# shemLamps.net
KiCad netlist of a schematic drawn in EAGLE
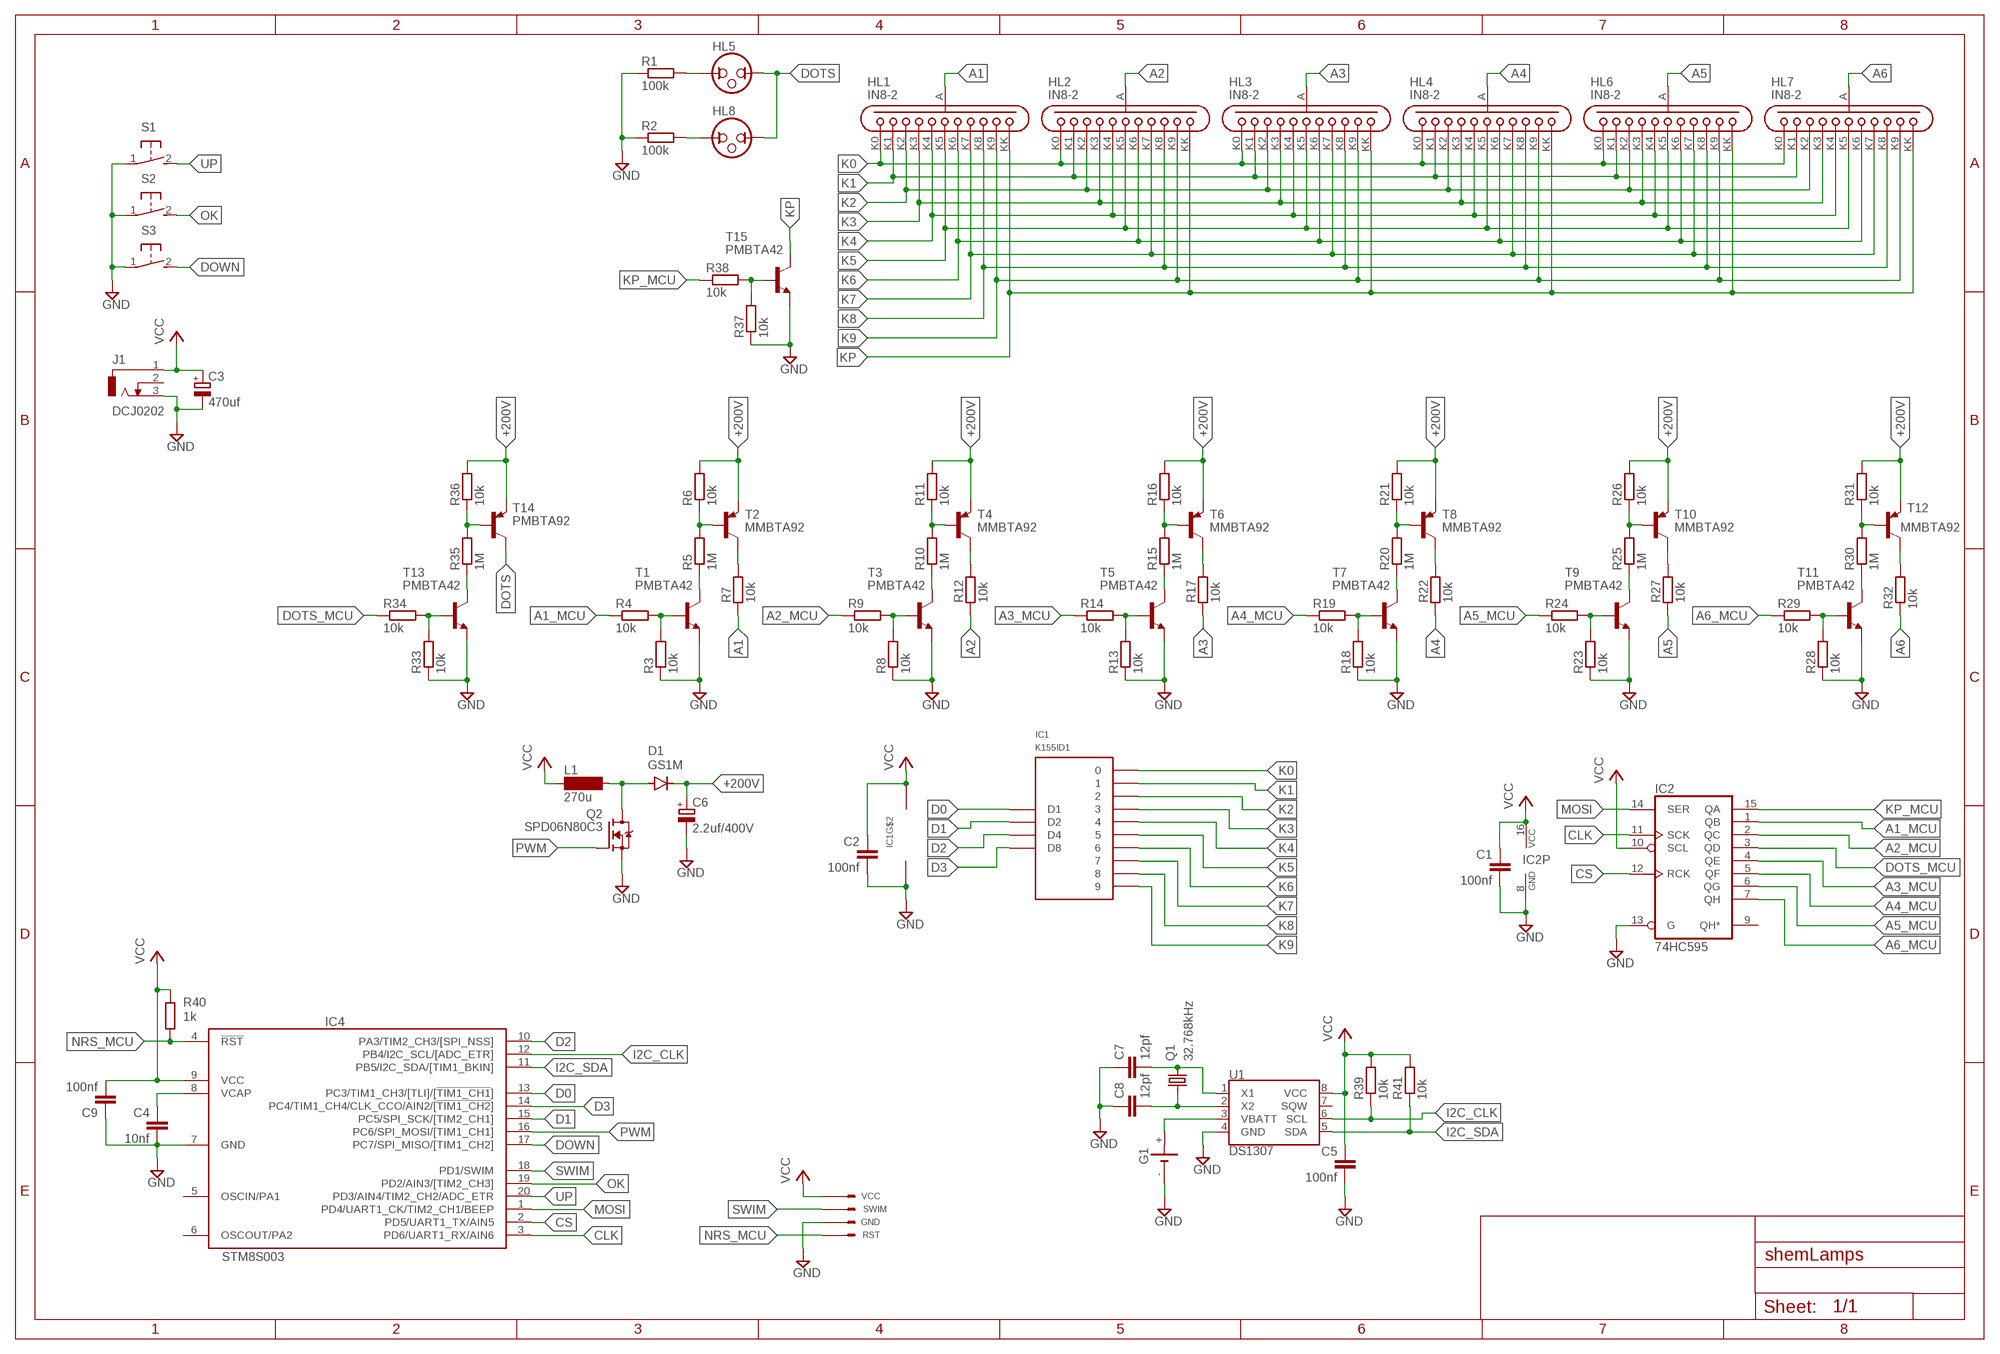
[diagram p0: schematic, sheet 1]

(export (version "E")
  (design (tool "Eeschema 10.0.6"))
  (components
    (comp (ref "C1")
      (value "100nf")
      (footprint "eagle-import:C0805")
      (libsource (lib "eagle-import") (part "CAP"))
    )
    (comp (ref "C2")
      (value "100nf")
      (footprint "eagle-import:C0805")
      (libsource (lib "eagle-import") (part "CAP"))
    )
    (comp (ref "C3")
      (value "470uf")
      (footprint "eagle-import:E3,5-8")
      (libsource (lib "eagle-import") (part "CPOL-EUE3.5-8"))
    )
    (comp (ref "C4")
      (value "10nf")
      (footprint "eagle-import:C0805")
      (libsource (lib "eagle-import") (part "CAP"))
    )
    (comp (ref "C5")
      (value "100nf")
      (footprint "eagle-import:C0805")
      (libsource (lib "eagle-import") (part "CAP"))
    )
    (comp (ref "C6")
      (value "2.2uf/400V")
      (footprint "eagle-import:E3,5-8")
      (libsource (lib "eagle-import") (part "CPOL-EUE3.5-8"))
    )
    (comp (ref "C7")
      (value "12pf")
      (footprint "eagle-import:C0805")
      (libsource (lib "eagle-import") (part "CAP"))
    )
    (comp (ref "C8")
      (value "12pf")
      (footprint "eagle-import:C0805")
      (libsource (lib "eagle-import") (part "CAP"))
    )
    (comp (ref "C9")
      (value "100nf")
      (footprint "eagle-import:C0805")
      (libsource (lib "eagle-import") (part "CAP"))
    )
    (comp (ref "D1")
      (value "GS1M")
      (footprint "eagle-import:DO-214AC")
      (libsource (lib "eagle-import") (part "DIODE-DO-214AC"))
    )
    (comp (ref "G1")
      (value "BATTERY")
      (footprint "eagle-import:CH291-1220LF_W")
      (libsource (lib "eagle-import") (part "BATTERY"))
    )
    (comp (ref "HL1")
      (value "IN8-2")
      (footprint "eagle-import:IN8-2")
      (libsource (lib "eagle-import") (part "IN8-2"))
    )
    (comp (ref "HL2")
      (value "IN8-2")
      (footprint "eagle-import:IN8-2")
      (libsource (lib "eagle-import") (part "IN8-2"))
    )
    (comp (ref "HL3")
      (value "IN8-2")
      (footprint "eagle-import:IN8-2")
      (libsource (lib "eagle-import") (part "IN8-2"))
    )
    (comp (ref "HL4")
      (value "IN8-2")
      (footprint "eagle-import:IN8-2")
      (libsource (lib "eagle-import") (part "IN8-2"))
    )
    (comp (ref "HL5")
      (value "NEON_LAMP")
      (footprint "eagle-import:NEON_LAMP")
      (libsource (lib "eagle-import") (part "NEON_LAMP"))
    )
    (comp (ref "HL6")
      (value "IN8-2")
      (footprint "eagle-import:IN8-2")
      (libsource (lib "eagle-import") (part "IN8-2"))
    )
    (comp (ref "HL7")
      (value "IN8-2")
      (footprint "eagle-import:IN8-2")
      (libsource (lib "eagle-import") (part "IN8-2"))
    )
    (comp (ref "HL8")
      (value "NEON_LAMP")
      (footprint "eagle-import:NEON_LAMP")
      (libsource (lib "eagle-import") (part "NEON_LAMP"))
    )
    (comp (ref "IC1")
      (value "K155ID1")
      (footprint "eagle-import:DIL16")
      (libsource (lib "eagle-import") (part "K155ID1"))
    )
    (comp (ref "IC2")
      (value "74HC595")
      (footprint "eagle-import:TSSOP16L")
      (libsource (lib "eagle-import") (part "74HC595"))
    )
    (comp (ref "IC4")
      (value "STM8S003")
      (footprint "eagle-import:TSSOP-20")
      (libsource (lib "eagle-import") (part "STM8S003"))
    )
    (comp (ref "J1")
      (value "DCJ0202")
      (footprint "eagle-import:DCJ0202")
      (libsource (lib "eagle-import") (part "DCJ0202"))
    )
    (comp (ref "L1")
      (value "270u")
      (footprint "eagle-import:BS11")
      (libsource (lib "eagle-import") (part "BS11"))
    )
    (comp (ref "Q1")
      (value "32.768kHz")
      (footprint "eagle-import:TC26H")
      (libsource (lib "eagle-import") (part "CRYSTALTC26H"))
    )
    (comp (ref "Q2")
      (value "SPD06N80C3")
      (footprint "eagle-import:TO252")
      (libsource (lib "eagle-import") (part "SPD06N80C3"))
    )
    (comp (ref "R1")
      (value "100k")
      (footprint "eagle-import:0207_10")
      (libsource (lib "eagle-import") (part "R-EU_0207/10"))
    )
    (comp (ref "R2")
      (value "100k")
      (footprint "eagle-import:0207_10")
      (libsource (lib "eagle-import") (part "R-EU_0207/10"))
    )
    (comp (ref "R3")
      (value "10k")
      (footprint "eagle-import:R0805")
      (libsource (lib "eagle-import") (part "RES"))
    )
    (comp (ref "R4")
      (value "10k")
      (footprint "eagle-import:R0805")
      (libsource (lib "eagle-import") (part "RES"))
    )
    (comp (ref "R5")
      (value "1M")
      (footprint "eagle-import:R0805")
      (libsource (lib "eagle-import") (part "RES"))
    )
    (comp (ref "R6")
      (value "10k")
      (footprint "eagle-import:R0805")
      (libsource (lib "eagle-import") (part "RES"))
    )
    (comp (ref "R7")
      (value "10k")
      (footprint "eagle-import:R0805")
      (libsource (lib "eagle-import") (part "RES"))
    )
    (comp (ref "R8")
      (value "10k")
      (footprint "eagle-import:R0805")
      (libsource (lib "eagle-import") (part "RES"))
    )
    (comp (ref "R9")
      (value "10k")
      (footprint "eagle-import:R0805")
      (libsource (lib "eagle-import") (part "RES"))
    )
    (comp (ref "R10")
      (value "1M")
      (footprint "eagle-import:R0805")
      (libsource (lib "eagle-import") (part "RES"))
    )
    (comp (ref "R11")
      (value "10k")
      (footprint "eagle-import:R0805")
      (libsource (lib "eagle-import") (part "RES"))
    )
    (comp (ref "R12")
      (value "10k")
      (footprint "eagle-import:R0805")
      (libsource (lib "eagle-import") (part "RES"))
    )
    (comp (ref "R13")
      (value "10k")
      (footprint "eagle-import:R0805")
      (libsource (lib "eagle-import") (part "RES"))
    )
    (comp (ref "R14")
      (value "10k")
      (footprint "eagle-import:R0805")
      (libsource (lib "eagle-import") (part "RES"))
    )
    (comp (ref "R15")
      (value "1M")
      (footprint "eagle-import:R0805")
      (libsource (lib "eagle-import") (part "RES"))
    )
    (comp (ref "R16")
      (value "10k")
      (footprint "eagle-import:R0805")
      (libsource (lib "eagle-import") (part "RES"))
    )
    (comp (ref "R17")
      (value "10k")
      (footprint "eagle-import:R0805")
      (libsource (lib "eagle-import") (part "RES"))
    )
    (comp (ref "R18")
      (value "10k")
      (footprint "eagle-import:R0805")
      (libsource (lib "eagle-import") (part "RES"))
    )
    (comp (ref "R19")
      (value "10k")
      (footprint "eagle-import:R0805")
      (libsource (lib "eagle-import") (part "RES"))
    )
    (comp (ref "R20")
      (value "1M")
      (footprint "eagle-import:R0805")
      (libsource (lib "eagle-import") (part "RES"))
    )
    (comp (ref "R21")
      (value "10k")
      (footprint "eagle-import:R0805")
      (libsource (lib "eagle-import") (part "RES"))
    )
    (comp (ref "R22")
      (value "10k")
      (footprint "eagle-import:R0805")
      (libsource (lib "eagle-import") (part "RES"))
    )
    (comp (ref "R23")
      (value "10k")
      (footprint "eagle-import:R0805")
      (libsource (lib "eagle-import") (part "RES"))
    )
    (comp (ref "R24")
      (value "10k")
      (footprint "eagle-import:R0805")
      (libsource (lib "eagle-import") (part "RES"))
    )
    (comp (ref "R25")
      (value "1M")
      (footprint "eagle-import:R0805")
      (libsource (lib "eagle-import") (part "RES"))
    )
    (comp (ref "R26")
      (value "10k")
      (footprint "eagle-import:R0805")
      (libsource (lib "eagle-import") (part "RES"))
    )
    (comp (ref "R27")
      (value "10k")
      (footprint "eagle-import:R0805")
      (libsource (lib "eagle-import") (part "RES"))
    )
    (comp (ref "R28")
      (value "10k")
      (footprint "eagle-import:R0805")
      (libsource (lib "eagle-import") (part "RES"))
    )
    (comp (ref "R29")
      (value "10k")
      (footprint "eagle-import:R0805")
      (libsource (lib "eagle-import") (part "RES"))
    )
    (comp (ref "R30")
      (value "1M")
      (footprint "eagle-import:R0805")
      (libsource (lib "eagle-import") (part "RES"))
    )
    (comp (ref "R31")
      (value "10k")
      (footprint "eagle-import:R0805")
      (libsource (lib "eagle-import") (part "RES"))
    )
    (comp (ref "R32")
      (value "10k")
      (footprint "eagle-import:R0805")
      (libsource (lib "eagle-import") (part "RES"))
    )
    (comp (ref "R33")
      (value "10k")
      (footprint "eagle-import:R0805")
      (libsource (lib "eagle-import") (part "RES"))
    )
    (comp (ref "R34")
      (value "10k")
      (footprint "eagle-import:R0805")
      (libsource (lib "eagle-import") (part "RES"))
    )
    (comp (ref "R35")
      (value "1M")
      (footprint "eagle-import:R0805")
      (libsource (lib "eagle-import") (part "RES"))
    )
    (comp (ref "R36")
      (value "10k")
      (footprint "eagle-import:R0805")
      (libsource (lib "eagle-import") (part "RES"))
    )
    (comp (ref "R37")
      (value "10k")
      (footprint "eagle-import:R0805")
      (libsource (lib "eagle-import") (part "RES"))
    )
    (comp (ref "R38")
      (value "10k")
      (footprint "eagle-import:R0805")
      (libsource (lib "eagle-import") (part "RES"))
    )
    (comp (ref "R39")
      (value "10k")
      (footprint "eagle-import:R0805")
      (libsource (lib "eagle-import") (part "RES"))
    )
    (comp (ref "R40")
      (value "1k")
      (footprint "eagle-import:R0805")
      (libsource (lib "eagle-import") (part "RES"))
    )
    (comp (ref "R41")
      (value "10k")
      (footprint "eagle-import:R0805")
      (libsource (lib "eagle-import") (part "RES"))
    )
    (comp (ref "S1")
      (value "31-XX")
      (footprint "eagle-import:B3F-31XX")
      (fields (field (name "MPN") "B3F-3100"))
      (libsource (lib "eagle-import") (part "31-XX"))
    )
    (comp (ref "S2")
      (value "31-XX")
      (footprint "eagle-import:B3F-31XX")
      (fields (field (name "MPN") "B3F-3100"))
      (libsource (lib "eagle-import") (part "31-XX"))
    )
    (comp (ref "S3")
      (value "31-XX")
      (footprint "eagle-import:B3F-31XX")
      (fields (field (name "MPN") "B3F-3100"))
      (libsource (lib "eagle-import") (part "31-XX"))
    )
    (comp (ref "SV1")
      (value "SWIM")
      (footprint "eagle-import:SWIM")
      (libsource (lib "eagle-import") (part "SWIM"))
    )
    (comp (ref "T1")
      (value "PMBTA42")
      (footprint "eagle-import:SOT23-BEC")
      (libsource (lib "eagle-import") (part "-NPN-SOT23-BECBC817-16"))
    )
    (comp (ref "T2")
      (value "MMBTA92")
      (footprint "eagle-import:SOT23-BEC")
      (libsource (lib "eagle-import") (part "-PNP-SOT23-BECBC807-16"))
    )
    (comp (ref "T3")
      (value "PMBTA42")
      (footprint "eagle-import:SOT23-BEC")
      (libsource (lib "eagle-import") (part "-NPN-SOT23-BECBC817-16"))
    )
    (comp (ref "T4")
      (value "MMBTA92")
      (footprint "eagle-import:SOT23-BEC")
      (libsource (lib "eagle-import") (part "-PNP-SOT23-BECBC807-16"))
    )
    (comp (ref "T5")
      (value "PMBTA42")
      (footprint "eagle-import:SOT23-BEC")
      (libsource (lib "eagle-import") (part "-NPN-SOT23-BECBC817-16"))
    )
    (comp (ref "T6")
      (value "MMBTA92")
      (footprint "eagle-import:SOT23-BEC")
      (libsource (lib "eagle-import") (part "-PNP-SOT23-BECBC807-16"))
    )
    (comp (ref "T7")
      (value "PMBTA42")
      (footprint "eagle-import:SOT23-BEC")
      (libsource (lib "eagle-import") (part "-NPN-SOT23-BECBC817-16"))
    )
    (comp (ref "T8")
      (value "MMBTA92")
      (footprint "eagle-import:SOT23-BEC")
      (libsource (lib "eagle-import") (part "-PNP-SOT23-BECBC807-16"))
    )
    (comp (ref "T9")
      (value "PMBTA42")
      (footprint "eagle-import:SOT23-BEC")
      (libsource (lib "eagle-import") (part "-NPN-SOT23-BECBC817-16"))
    )
    (comp (ref "T10")
      (value "MMBTA92")
      (footprint "eagle-import:SOT23-BEC")
      (libsource (lib "eagle-import") (part "-PNP-SOT23-BECBC807-16"))
    )
    (comp (ref "T11")
      (value "PMBTA42")
      (footprint "eagle-import:SOT23-BEC")
      (libsource (lib "eagle-import") (part "-NPN-SOT23-BECBC817-16"))
    )
    (comp (ref "T12")
      (value "MMBTA92")
      (footprint "eagle-import:SOT23-BEC")
      (libsource (lib "eagle-import") (part "-PNP-SOT23-BECBC807-16"))
    )
    (comp (ref "T13")
      (value "PMBTA42")
      (footprint "eagle-import:SOT23-BEC")
      (libsource (lib "eagle-import") (part "-NPN-SOT23-BECBC817-16"))
    )
    (comp (ref "T14")
      (value "PMBTA92")
      (footprint "eagle-import:SOT23-BEC")
      (libsource (lib "eagle-import") (part "-PNP-SOT23-BECBC807-16"))
    )
    (comp (ref "T15")
      (value "PMBTA42")
      (footprint "eagle-import:SOT23-BEC")
      (libsource (lib "eagle-import") (part "-NPN-SOT23-BECBC817-16"))
    )
    (comp (ref "U1")
      (value "DS1307")
      (footprint "eagle-import:SO08")
      (libsource (lib "eagle-import") (part "DS1307"))
    )
  )
  (nets
    (net (code "1") (name "+200V") (class "Default")
      (node (ref "C6") (pin "+") (pinfunction "+_+") (pintype "passive"))
      (node (ref "D1") (pin "C") (pinfunction "C_C") (pintype "passive"))
      (node (ref "R11") (pin "2") (pinfunction "2_2") (pintype "passive"))
      (node (ref "R16") (pin "2") (pinfunction "2_2") (pintype "passive"))
      (node (ref "R21") (pin "2") (pinfunction "2_2") (pintype "passive"))
      (node (ref "R26") (pin "2") (pinfunction "2_2") (pintype "passive"))
      (node (ref "R31") (pin "2") (pinfunction "2_2") (pintype "passive"))
      (node (ref "R36") (pin "2") (pinfunction "2_2") (pintype "passive"))
      (node (ref "R6") (pin "2") (pinfunction "2_2") (pintype "passive"))
      (node (ref "T10") (pin "E") (pinfunction "E_E") (pintype "passive"))
      (node (ref "T12") (pin "E") (pinfunction "E_E") (pintype "passive"))
      (node (ref "T14") (pin "E") (pinfunction "E_E") (pintype "passive"))
      (node (ref "T2") (pin "E") (pinfunction "E_E") (pintype "passive"))
      (node (ref "T4") (pin "E") (pinfunction "E_E") (pintype "passive"))
      (node (ref "T6") (pin "E") (pinfunction "E_E") (pintype "passive"))
      (node (ref "T8") (pin "E") (pinfunction "E_E") (pintype "passive"))
    )
    (net (code "2") (name "A1") (class "Default")
      (node (ref "HL1") (pin "A") (pinfunction "A_A") (pintype "passive"))
      (node (ref "R7") (pin "1") (pinfunction "1_1") (pintype "passive"))
    )
    (net (code "3") (name "A1_MCU") (class "Default")
      (node (ref "IC2") (pin "1") (pinfunction "QB_1") (pintype "tri_state"))
      (node (ref "R4") (pin "1") (pinfunction "1_1") (pintype "passive"))
    )
    (net (code "4") (name "A2") (class "Default")
      (node (ref "HL2") (pin "A") (pinfunction "A_A") (pintype "passive"))
      (node (ref "R12") (pin "1") (pinfunction "1_1") (pintype "passive"))
    )
    (net (code "5") (name "A2_MCU") (class "Default")
      (node (ref "IC2") (pin "2") (pinfunction "QC_2") (pintype "tri_state"))
      (node (ref "R9") (pin "1") (pinfunction "1_1") (pintype "passive"))
    )
    (net (code "6") (name "A3") (class "Default")
      (node (ref "HL3") (pin "A") (pinfunction "A_A") (pintype "passive"))
      (node (ref "R17") (pin "1") (pinfunction "1_1") (pintype "passive"))
    )
    (net (code "7") (name "A3_MCU") (class "Default")
      (node (ref "IC2") (pin "4") (pinfunction "QE_4") (pintype "tri_state"))
      (node (ref "R14") (pin "1") (pinfunction "1_1") (pintype "passive"))
    )
    (net (code "8") (name "A4") (class "Default")
      (node (ref "HL4") (pin "A") (pinfunction "A_A") (pintype "passive"))
      (node (ref "R22") (pin "1") (pinfunction "1_1") (pintype "passive"))
    )
    (net (code "9") (name "A4_MCU") (class "Default")
      (node (ref "IC2") (pin "5") (pinfunction "QF_5") (pintype "tri_state"))
      (node (ref "R19") (pin "1") (pinfunction "1_1") (pintype "passive"))
    )
    (net (code "10") (name "A5") (class "Default")
      (node (ref "HL6") (pin "A") (pinfunction "A_A") (pintype "passive"))
      (node (ref "R27") (pin "1") (pinfunction "1_1") (pintype "passive"))
    )
    (net (code "11") (name "A5_MCU") (class "Default")
      (node (ref "IC2") (pin "6") (pinfunction "QG_6") (pintype "tri_state"))
      (node (ref "R24") (pin "1") (pinfunction "1_1") (pintype "passive"))
    )
    (net (code "12") (name "A6") (class "Default")
      (node (ref "HL7") (pin "A") (pinfunction "A_A") (pintype "passive"))
      (node (ref "R32") (pin "1") (pinfunction "1_1") (pintype "passive"))
    )
    (net (code "13") (name "A6_MCU") (class "Default")
      (node (ref "IC2") (pin "7") (pinfunction "QH_7") (pintype "tri_state"))
      (node (ref "R29") (pin "1") (pinfunction "1_1") (pintype "passive"))
    )
    (net (code "14") (name "CLK") (class "Default")
      (node (ref "IC2") (pin "11") (pinfunction "SCK_11") (pintype "input"))
      (node (ref "IC4") (pin "3") (pinfunction "PD6/UART1_RX/AIN6_3") (pintype "bidirectional"))
    )
    (net (code "15") (name "CS") (class "Default")
      (node (ref "IC2") (pin "12") (pinfunction "RCK_12") (pintype "input"))
      (node (ref "IC4") (pin "2") (pinfunction "PD5/UART1_TX/AIN5_2") (pintype "bidirectional"))
    )
    (net (code "16") (name "D0") (class "Default")
      (node (ref "IC1") (pin "3") (pinfunction "D1_3") (pintype "input"))
      (node (ref "IC4") (pin "13") (pinfunction "PC3/TIM1_CH3/[TLI]/[~{TIM1_CH1}]_13") (pintype "bidirectional"))
    )
    (net (code "17") (name "D1") (class "Default")
      (node (ref "IC1") (pin "6") (pinfunction "D2_6") (pintype "input"))
      (node (ref "IC4") (pin "15") (pinfunction "PC5/SPI_SCK/[TIM2_CH1]_15") (pintype "bidirectional"))
    )
    (net (code "18") (name "D2") (class "Default")
      (node (ref "IC1") (pin "7") (pinfunction "D4_7") (pintype "input"))
      (node (ref "IC4") (pin "10") (pinfunction "PA3/TIM2_CH3/[SPI_NSS]_10") (pintype "bidirectional"))
    )
    (net (code "19") (name "D3") (class "Default")
      (node (ref "IC1") (pin "4") (pinfunction "D8_4") (pintype "input"))
      (node (ref "IC4") (pin "14") (pinfunction "PC4/TIM1_CH4/CLK_CCO/AIN2/[~{TIM1_CH2}]_14") (pintype "bidirectional"))
    )
    (net (code "20") (name "DOTS") (class "Default")
      (node (ref "HL5") (pin "2") (pinfunction "2_2") (pintype "passive"))
      (node (ref "HL8") (pin "2") (pinfunction "2_2") (pintype "passive"))
      (node (ref "T14") (pin "C") (pinfunction "C_C") (pintype "passive"))
    )
    (net (code "21") (name "DOTS_MCU") (class "Default")
      (node (ref "IC2") (pin "3") (pinfunction "QD_3") (pintype "tri_state"))
      (node (ref "R34") (pin "1") (pinfunction "1_1") (pintype "passive"))
    )
    (net (code "22") (name "DOWN") (class "Default")
      (node (ref "IC4") (pin "17") (pinfunction "PC7/SPI_MISO/[TIM1_CH2]_17") (pintype "bidirectional"))
      (node (ref "S3") (pin "2") (pinfunction "S_2") (pintype "passive"))
    )
    (net (code "23") (name "GND") (class "Default")
      (node (ref "C1") (pin "2") (pinfunction "2_2") (pintype "passive"))
      (node (ref "C2") (pin "2") (pinfunction "2_2") (pintype "passive"))
      (node (ref "C3") (pin "-") (pinfunction "-_-") (pintype "passive"))
      (node (ref "C4") (pin "2") (pinfunction "2_2") (pintype "passive"))
      (node (ref "C5") (pin "2") (pinfunction "2_2") (pintype "passive"))
      (node (ref "C6") (pin "-") (pinfunction "-_-") (pintype "passive"))
      (node (ref "C7") (pin "1") (pinfunction "1_1") (pintype "passive"))
      (node (ref "C8") (pin "1") (pinfunction "1_1") (pintype "passive"))
      (node (ref "C9") (pin "1") (pinfunction "1_1") (pintype "passive"))
      (node (ref "G1") (pin "-") (pinfunction "-_-") (pintype "passive"))
      (node (ref "IC1") (pin "12") (pinfunction "GND_12") (pintype "power_in"))
      (node (ref "IC2") (pin "13") (pinfunction "G_13") (pintype "input"))
      (node (ref "IC2") (pin "8") (pinfunction "GND_8") (pintype "power_in"))
      (node (ref "IC4") (pin "7") (pinfunction "GND_7") (pintype "power_in"))
      (node (ref "J1") (pin "3") (pinfunction "3_3") (pintype "passive"))
      (node (ref "Q2") (pin "2") (pinfunction "S_2") (pintype "passive"))
      (node (ref "R1") (pin "1") (pinfunction "1_1") (pintype "passive"))
      (node (ref "R13") (pin "1") (pinfunction "1_1") (pintype "passive"))
      (node (ref "R18") (pin "1") (pinfunction "1_1") (pintype "passive"))
      (node (ref "R2") (pin "1") (pinfunction "1_1") (pintype "passive"))
      (node (ref "R23") (pin "1") (pinfunction "1_1") (pintype "passive"))
      (node (ref "R28") (pin "1") (pinfunction "1_1") (pintype "passive"))
      (node (ref "R3") (pin "1") (pinfunction "1_1") (pintype "passive"))
      (node (ref "R33") (pin "1") (pinfunction "1_1") (pintype "passive"))
      (node (ref "R37") (pin "1") (pinfunction "1_1") (pintype "passive"))
      (node (ref "R8") (pin "1") (pinfunction "1_1") (pintype "passive"))
      (node (ref "S1") (pin "1") (pinfunction "P_1") (pintype "passive"))
      (node (ref "S2") (pin "1") (pinfunction "P_1") (pintype "passive"))
      (node (ref "S3") (pin "1") (pinfunction "P_1") (pintype "passive"))
      (node (ref "SV1") (pin "GND") (pinfunction "GND_GND") (pintype "power_in"))
      (node (ref "T1") (pin "E") (pinfunction "E_E") (pintype "passive"))
      (node (ref "T11") (pin "E") (pinfunction "E_E") (pintype "passive"))
      (node (ref "T13") (pin "E") (pinfunction "E_E") (pintype "passive"))
      (node (ref "T15") (pin "E") (pinfunction "E_E") (pintype "passive"))
      (node (ref "T3") (pin "E") (pinfunction "E_E") (pintype "passive"))
      (node (ref "T5") (pin "E") (pinfunction "E_E") (pintype "passive"))
      (node (ref "T7") (pin "E") (pinfunction "E_E") (pintype "passive"))
      (node (ref "T9") (pin "E") (pinfunction "E_E") (pintype "passive"))
      (node (ref "U1") (pin "4") (pinfunction "GND_4") (pintype "bidirectional"))
    )
    (net (code "24") (name "I2C_CLK") (class "Default")
      (node (ref "IC4") (pin "12") (pinfunction "PB4/I2C_SCL/[ADC_ETR]_12") (pintype "bidirectional"))
      (node (ref "R39") (pin "1") (pinfunction "1_1") (pintype "passive"))
      (node (ref "U1") (pin "6") (pinfunction "SCL_6") (pintype "bidirectional"))
    )
    (net (code "25") (name "I2C_SDA") (class "Default")
      (node (ref "IC4") (pin "11") (pinfunction "PB5/I2C_SDA/[TIM1_BKIN]_11") (pintype "bidirectional"))
      (node (ref "R41") (pin "1") (pinfunction "1_1") (pintype "passive"))
      (node (ref "U1") (pin "5") (pinfunction "SDA_5") (pintype "bidirectional"))
    )
    (net (code "26") (name "K0") (class "Default")
      (node (ref "HL1") (pin "K0") (pinfunction "K0_K0") (pintype "passive"))
      (node (ref "HL2") (pin "K0") (pinfunction "K0_K0") (pintype "passive"))
      (node (ref "HL3") (pin "K0") (pinfunction "K0_K0") (pintype "passive"))
      (node (ref "HL4") (pin "K0") (pinfunction "K0_K0") (pintype "passive"))
      (node (ref "HL6") (pin "K0") (pinfunction "K0_K0") (pintype "passive"))
      (node (ref "HL7") (pin "K0") (pinfunction "K0_K0") (pintype "passive"))
      (node (ref "IC1") (pin "16") (pinfunction "0_16") (pintype "output"))
    )
    (net (code "27") (name "K1") (class "Default")
      (node (ref "HL1") (pin "K1") (pinfunction "K1_K1") (pintype "passive"))
      (node (ref "HL2") (pin "K1") (pinfunction "K1_K1") (pintype "passive"))
      (node (ref "HL3") (pin "K1") (pinfunction "K1_K1") (pintype "passive"))
      (node (ref "HL4") (pin "K1") (pinfunction "K1_K1") (pintype "passive"))
      (node (ref "HL6") (pin "K1") (pinfunction "K1_K1") (pintype "passive"))
      (node (ref "HL7") (pin "K1") (pinfunction "K1_K1") (pintype "passive"))
      (node (ref "IC1") (pin "15") (pinfunction "1_15") (pintype "output"))
    )
    (net (code "28") (name "K2") (class "Default")
      (node (ref "HL1") (pin "K2") (pinfunction "K2_K2") (pintype "passive"))
      (node (ref "HL2") (pin "K2") (pinfunction "K2_K2") (pintype "passive"))
      (node (ref "HL3") (pin "K2") (pinfunction "K2_K2") (pintype "passive"))
      (node (ref "HL4") (pin "K2") (pinfunction "K2_K2") (pintype "passive"))
      (node (ref "HL6") (pin "K2") (pinfunction "K2_K2") (pintype "passive"))
      (node (ref "HL7") (pin "K2") (pinfunction "K2_K2") (pintype "passive"))
      (node (ref "IC1") (pin "8") (pinfunction "2_8") (pintype "output"))
    )
    (net (code "29") (name "K3") (class "Default")
      (node (ref "HL1") (pin "K3") (pinfunction "K3_K3") (pintype "passive"))
      (node (ref "HL2") (pin "K3") (pinfunction "K3_K3") (pintype "passive"))
      (node (ref "HL3") (pin "K3") (pinfunction "K3_K3") (pintype "passive"))
      (node (ref "HL4") (pin "K3") (pinfunction "K3_K3") (pintype "passive"))
      (node (ref "HL6") (pin "K3") (pinfunction "K3_K3") (pintype "passive"))
      (node (ref "HL7") (pin "K3") (pinfunction "K3_K3") (pintype "passive"))
      (node (ref "IC1") (pin "9") (pinfunction "3_9") (pintype "output"))
    )
    (net (code "30") (name "K4") (class "Default")
      (node (ref "HL1") (pin "K4") (pinfunction "K4_K4") (pintype "passive"))
      (node (ref "HL2") (pin "K4") (pinfunction "K4_K4") (pintype "passive"))
      (node (ref "HL3") (pin "K4") (pinfunction "K4_K4") (pintype "passive"))
      (node (ref "HL4") (pin "K4") (pinfunction "K4_K4") (pintype "passive"))
      (node (ref "HL6") (pin "K4") (pinfunction "K4_K4") (pintype "passive"))
      (node (ref "HL7") (pin "K4") (pinfunction "K4_K4") (pintype "passive"))
      (node (ref "IC1") (pin "13") (pinfunction "4_13") (pintype "output"))
    )
    (net (code "31") (name "K5") (class "Default")
      (node (ref "HL1") (pin "K5") (pinfunction "K5_K5") (pintype "passive"))
      (node (ref "HL2") (pin "K5") (pinfunction "K5_K5") (pintype "passive"))
      (node (ref "HL3") (pin "K5") (pinfunction "K5_K5") (pintype "passive"))
      (node (ref "HL4") (pin "K5") (pinfunction "K5_K5") (pintype "passive"))
      (node (ref "HL6") (pin "K5") (pinfunction "K5_K5") (pintype "passive"))
      (node (ref "HL7") (pin "K5") (pinfunction "K5_K5") (pintype "passive"))
      (node (ref "IC1") (pin "14") (pinfunction "5_14") (pintype "output"))
    )
    (net (code "32") (name "K6") (class "Default")
      (node (ref "HL1") (pin "K6") (pinfunction "K6_K6") (pintype "passive"))
      (node (ref "HL2") (pin "K6") (pinfunction "K6_K6") (pintype "passive"))
      (node (ref "HL3") (pin "K6") (pinfunction "K6_K6") (pintype "passive"))
      (node (ref "HL4") (pin "K6") (pinfunction "K6_K6") (pintype "passive"))
      (node (ref "HL6") (pin "K6") (pinfunction "K6_K6") (pintype "passive"))
      (node (ref "HL7") (pin "K6") (pinfunction "K6_K6") (pintype "passive"))
      (node (ref "IC1") (pin "11") (pinfunction "6_11") (pintype "output"))
    )
    (net (code "33") (name "K7") (class "Default")
      (node (ref "HL1") (pin "K7") (pinfunction "K7_K7") (pintype "passive"))
      (node (ref "HL2") (pin "K7") (pinfunction "K7_K7") (pintype "passive"))
      (node (ref "HL3") (pin "K7") (pinfunction "K7_K7") (pintype "passive"))
      (node (ref "HL4") (pin "K7") (pinfunction "K7_K7") (pintype "passive"))
      (node (ref "HL6") (pin "K7") (pinfunction "K7_K7") (pintype "passive"))
      (node (ref "HL7") (pin "K7") (pinfunction "K7_K7") (pintype "passive"))
      (node (ref "IC1") (pin "10") (pinfunction "7_10") (pintype "output"))
    )
    (net (code "34") (name "K8") (class "Default")
      (node (ref "HL1") (pin "K8") (pinfunction "K8_K8") (pintype "passive"))
      (node (ref "HL2") (pin "K8") (pinfunction "K8_K8") (pintype "passive"))
      (node (ref "HL3") (pin "K8") (pinfunction "K8_K8") (pintype "passive"))
      (node (ref "HL4") (pin "K8") (pinfunction "K8_K8") (pintype "passive"))
      (node (ref "HL6") (pin "K8") (pinfunction "K8_K8") (pintype "passive"))
      (node (ref "HL7") (pin "K8") (pinfunction "K8_K8") (pintype "passive"))
      (node (ref "IC1") (pin "1") (pinfunction "8_1") (pintype "output"))
    )
    (net (code "35") (name "K9") (class "Default")
      (node (ref "HL1") (pin "K9") (pinfunction "K9_K9") (pintype "passive"))
      (node (ref "HL2") (pin "K9") (pinfunction "K9_K9") (pintype "passive"))
      (node (ref "HL3") (pin "K9") (pinfunction "K9_K9") (pintype "passive"))
      (node (ref "HL4") (pin "K9") (pinfunction "K9_K9") (pintype "passive"))
      (node (ref "HL6") (pin "K9") (pinfunction "K9_K9") (pintype "passive"))
      (node (ref "HL7") (pin "K9") (pinfunction "K9_K9") (pintype "passive"))
      (node (ref "IC1") (pin "2") (pinfunction "9_2") (pintype "output"))
    )
    (net (code "36") (name "KP") (class "Default")
      (node (ref "HL1") (pin "KK") (pinfunction "KK_KK") (pintype "passive"))
      (node (ref "HL2") (pin "KK") (pinfunction "KK_KK") (pintype "passive"))
      (node (ref "HL3") (pin "KK") (pinfunction "KK_KK") (pintype "passive"))
      (node (ref "HL4") (pin "KK") (pinfunction "KK_KK") (pintype "passive"))
      (node (ref "HL6") (pin "KK") (pinfunction "KK_KK") (pintype "passive"))
      (node (ref "HL7") (pin "KK") (pinfunction "KK_KK") (pintype "passive"))
      (node (ref "T15") (pin "C") (pinfunction "C_C") (pintype "passive"))
    )
    (net (code "37") (name "KP_MCU") (class "Default")
      (node (ref "IC2") (pin "15") (pinfunction "QA_15") (pintype "tri_state"))
      (node (ref "R38") (pin "1") (pinfunction "1_1") (pintype "passive"))
    )
    (net (code "38") (name "MOSI") (class "Default")
      (node (ref "IC2") (pin "14") (pinfunction "SER_14") (pintype "input"))
      (node (ref "IC4") (pin "1") (pinfunction "PD4/UART1_CK/TIM2_CH1/BEEP_1") (pintype "bidirectional"))
    )
    (net (code "39") (name "NRS_MCU") (class "Default")
      (node (ref "IC4") (pin "4") (pinfunction "~{RST}_4") (pintype "input"))
      (node (ref "R40") (pin "1") (pinfunction "1_1") (pintype "passive"))
      (node (ref "SV1") (pin "NRS") (pinfunction "RST_NRS") (pintype "bidirectional"))
    )
    (net (code "40") (name "Net-(HL5-Pad1)") (class "Default")
      (node (ref "HL5") (pin "1") (pinfunction "1_1") (pintype "passive"))
      (node (ref "R1") (pin "2") (pinfunction "2_2") (pintype "passive"))
    )
    (net (code "41") (name "Net-(HL8-Pad1)") (class "Default")
      (node (ref "HL8") (pin "1") (pinfunction "1_1") (pintype "passive"))
      (node (ref "R2") (pin "2") (pinfunction "2_2") (pintype "passive"))
    )
    (net (code "42") (name "Net-(IC4-VCAP)") (class "Default")
      (node (ref "C4") (pin "1") (pinfunction "1_1") (pintype "passive"))
      (node (ref "IC4") (pin "8") (pinfunction "VCAP_8") (pintype "input"))
    )
    (net (code "43") (name "Net-(Q2-D)") (class "Default")
      (node (ref "D1") (pin "A") (pinfunction "A_A") (pintype "passive"))
      (node (ref "L1") (pin "2") (pinfunction "2_2") (pintype "passive"))
      (node (ref "Q2") (pin "3") (pinfunction "D_3") (pintype "passive"))
    )
    (net (code "44") (name "Net-(R3-Pad2)") (class "Default")
      (node (ref "R3") (pin "2") (pinfunction "2_2") (pintype "passive"))
      (node (ref "R4") (pin "2") (pinfunction "2_2") (pintype "passive"))
      (node (ref "T1") (pin "B") (pinfunction "B_B") (pintype "passive"))
    )
    (net (code "45") (name "Net-(R5-Pad1)") (class "Default")
      (node (ref "R5") (pin "1") (pinfunction "1_1") (pintype "passive"))
      (node (ref "T1") (pin "C") (pinfunction "C_C") (pintype "passive"))
    )
    (net (code "46") (name "Net-(R5-Pad2)") (class "Default")
      (node (ref "R5") (pin "2") (pinfunction "2_2") (pintype "passive"))
      (node (ref "R6") (pin "1") (pinfunction "1_1") (pintype "passive"))
      (node (ref "T2") (pin "B") (pinfunction "B_B") (pintype "passive"))
    )
    (net (code "47") (name "Net-(R7-Pad2)") (class "Default")
      (node (ref "R7") (pin "2") (pinfunction "2_2") (pintype "passive"))
      (node (ref "T2") (pin "C") (pinfunction "C_C") (pintype "passive"))
    )
    (net (code "48") (name "Net-(R8-Pad2)") (class "Default")
      (node (ref "R8") (pin "2") (pinfunction "2_2") (pintype "passive"))
      (node (ref "R9") (pin "2") (pinfunction "2_2") (pintype "passive"))
      (node (ref "T3") (pin "B") (pinfunction "B_B") (pintype "passive"))
    )
    (net (code "49") (name "Net-(R10-Pad1)") (class "Default")
      (node (ref "R10") (pin "1") (pinfunction "1_1") (pintype "passive"))
      (node (ref "T3") (pin "C") (pinfunction "C_C") (pintype "passive"))
    )
    (net (code "50") (name "Net-(R10-Pad2)") (class "Default")
      (node (ref "R10") (pin "2") (pinfunction "2_2") (pintype "passive"))
      (node (ref "R11") (pin "1") (pinfunction "1_1") (pintype "passive"))
      (node (ref "T4") (pin "B") (pinfunction "B_B") (pintype "passive"))
    )
    (net (code "51") (name "Net-(R12-Pad2)") (class "Default")
      (node (ref "R12") (pin "2") (pinfunction "2_2") (pintype "passive"))
      (node (ref "T4") (pin "C") (pinfunction "C_C") (pintype "passive"))
    )
    (net (code "52") (name "Net-(R13-Pad2)") (class "Default")
      (node (ref "R13") (pin "2") (pinfunction "2_2") (pintype "passive"))
      (node (ref "R14") (pin "2") (pinfunction "2_2") (pintype "passive"))
      (node (ref "T5") (pin "B") (pinfunction "B_B") (pintype "passive"))
    )
    (net (code "53") (name "Net-(R15-Pad1)") (class "Default")
      (node (ref "R15") (pin "1") (pinfunction "1_1") (pintype "passive"))
      (node (ref "T5") (pin "C") (pinfunction "C_C") (pintype "passive"))
    )
    (net (code "54") (name "Net-(R15-Pad2)") (class "Default")
      (node (ref "R15") (pin "2") (pinfunction "2_2") (pintype "passive"))
      (node (ref "R16") (pin "1") (pinfunction "1_1") (pintype "passive"))
      (node (ref "T6") (pin "B") (pinfunction "B_B") (pintype "passive"))
    )
    (net (code "55") (name "Net-(R17-Pad2)") (class "Default")
      (node (ref "R17") (pin "2") (pinfunction "2_2") (pintype "passive"))
      (node (ref "T6") (pin "C") (pinfunction "C_C") (pintype "passive"))
    )
    (net (code "56") (name "Net-(R18-Pad2)") (class "Default")
      (node (ref "R18") (pin "2") (pinfunction "2_2") (pintype "passive"))
      (node (ref "R19") (pin "2") (pinfunction "2_2") (pintype "passive"))
      (node (ref "T7") (pin "B") (pinfunction "B_B") (pintype "passive"))
    )
    (net (code "57") (name "Net-(R20-Pad1)") (class "Default")
      (node (ref "R20") (pin "1") (pinfunction "1_1") (pintype "passive"))
      (node (ref "T7") (pin "C") (pinfunction "C_C") (pintype "passive"))
    )
    (net (code "58") (name "Net-(R20-Pad2)") (class "Default")
      (node (ref "R20") (pin "2") (pinfunction "2_2") (pintype "passive"))
      (node (ref "R21") (pin "1") (pinfunction "1_1") (pintype "passive"))
      (node (ref "T8") (pin "B") (pinfunction "B_B") (pintype "passive"))
    )
    (net (code "59") (name "Net-(R22-Pad2)") (class "Default")
      (node (ref "R22") (pin "2") (pinfunction "2_2") (pintype "passive"))
      (node (ref "T8") (pin "C") (pinfunction "C_C") (pintype "passive"))
    )
    (net (code "60") (name "Net-(R23-Pad2)") (class "Default")
      (node (ref "R23") (pin "2") (pinfunction "2_2") (pintype "passive"))
      (node (ref "R24") (pin "2") (pinfunction "2_2") (pintype "passive"))
      (node (ref "T9") (pin "B") (pinfunction "B_B") (pintype "passive"))
    )
    (net (code "61") (name "Net-(R25-Pad1)") (class "Default")
      (node (ref "R25") (pin "1") (pinfunction "1_1") (pintype "passive"))
      (node (ref "T9") (pin "C") (pinfunction "C_C") (pintype "passive"))
    )
    (net (code "62") (name "Net-(R25-Pad2)") (class "Default")
      (node (ref "R25") (pin "2") (pinfunction "2_2") (pintype "passive"))
      (node (ref "R26") (pin "1") (pinfunction "1_1") (pintype "passive"))
      (node (ref "T10") (pin "B") (pinfunction "B_B") (pintype "passive"))
    )
    (net (code "63") (name "Net-(R27-Pad2)") (class "Default")
      (node (ref "R27") (pin "2") (pinfunction "2_2") (pintype "passive"))
      (node (ref "T10") (pin "C") (pinfunction "C_C") (pintype "passive"))
    )
    (net (code "64") (name "Net-(R28-Pad2)") (class "Default")
      (node (ref "R28") (pin "2") (pinfunction "2_2") (pintype "passive"))
      (node (ref "R29") (pin "2") (pinfunction "2_2") (pintype "passive"))
      (node (ref "T11") (pin "B") (pinfunction "B_B") (pintype "passive"))
    )
    (net (code "65") (name "Net-(R30-Pad1)") (class "Default")
      (node (ref "R30") (pin "1") (pinfunction "1_1") (pintype "passive"))
      (node (ref "T11") (pin "C") (pinfunction "C_C") (pintype "passive"))
    )
    (net (code "66") (name "Net-(R30-Pad2)") (class "Default")
      (node (ref "R30") (pin "2") (pinfunction "2_2") (pintype "passive"))
      (node (ref "R31") (pin "1") (pinfunction "1_1") (pintype "passive"))
      (node (ref "T12") (pin "B") (pinfunction "B_B") (pintype "passive"))
    )
    (net (code "67") (name "Net-(R32-Pad2)") (class "Default")
      (node (ref "R32") (pin "2") (pinfunction "2_2") (pintype "passive"))
      (node (ref "T12") (pin "C") (pinfunction "C_C") (pintype "passive"))
    )
    (net (code "68") (name "Net-(R33-Pad2)") (class "Default")
      (node (ref "R33") (pin "2") (pinfunction "2_2") (pintype "passive"))
      (node (ref "R34") (pin "2") (pinfunction "2_2") (pintype "passive"))
      (node (ref "T13") (pin "B") (pinfunction "B_B") (pintype "passive"))
    )
    (net (code "69") (name "Net-(R35-Pad1)") (class "Default")
      (node (ref "R35") (pin "1") (pinfunction "1_1") (pintype "passive"))
      (node (ref "T13") (pin "C") (pinfunction "C_C") (pintype "passive"))
    )
    (net (code "70") (name "Net-(R35-Pad2)") (class "Default")
      (node (ref "R35") (pin "2") (pinfunction "2_2") (pintype "passive"))
      (node (ref "R36") (pin "1") (pinfunction "1_1") (pintype "passive"))
      (node (ref "T14") (pin "B") (pinfunction "B_B") (pintype "passive"))
    )
    (net (code "71") (name "Net-(R37-Pad2)") (class "Default")
      (node (ref "R37") (pin "2") (pinfunction "2_2") (pintype "passive"))
      (node (ref "R38") (pin "2") (pinfunction "2_2") (pintype "passive"))
      (node (ref "T15") (pin "B") (pinfunction "B_B") (pintype "passive"))
    )
    (net (code "72") (name "Net-(U1-VBATT)") (class "Default")
      (node (ref "G1") (pin "+") (pinfunction "+_+") (pintype "passive"))
      (node (ref "U1") (pin "3") (pinfunction "VBATT_3") (pintype "bidirectional"))
    )
    (net (code "73") (name "Net-(U1-X1)") (class "Default")
      (node (ref "C7") (pin "2") (pinfunction "2_2") (pintype "passive"))
      (node (ref "Q1") (pin "1") (pinfunction "1_1") (pintype "passive"))
      (node (ref "U1") (pin "1") (pinfunction "X1_1") (pintype "bidirectional"))
    )
    (net (code "74") (name "Net-(U1-X2)") (class "Default")
      (node (ref "C8") (pin "2") (pinfunction "2_2") (pintype "passive"))
      (node (ref "Q1") (pin "2") (pinfunction "2_2") (pintype "passive"))
      (node (ref "U1") (pin "2") (pinfunction "X2_2") (pintype "bidirectional"))
    )
    (net (code "75") (name "OK") (class "Default")
      (node (ref "IC4") (pin "19") (pinfunction "PD2/AIN3/[TIM2_CH3]_19") (pintype "bidirectional"))
      (node (ref "S2") (pin "2") (pinfunction "S_2") (pintype "passive"))
    )
    (net (code "76") (name "PWM") (class "Default")
      (node (ref "IC4") (pin "16") (pinfunction "PC6/SPI_MOSI/[TIM1_CH1]_16") (pintype "bidirectional"))
      (node (ref "Q2") (pin "1") (pinfunction "G_1") (pintype "passive"))
    )
    (net (code "77") (name "SWIM") (class "Default")
      (node (ref "IC4") (pin "18") (pinfunction "PD1/SWIM_18") (pintype "bidirectional"))
      (node (ref "SV1") (pin "SWIM") (pinfunction "SWIM_SWIM") (pintype "bidirectional"))
    )
    (net (code "78") (name "UP") (class "Default")
      (node (ref "IC4") (pin "20") (pinfunction "PD3/AIN4/TIM2_CH2/ADC_ETR_20") (pintype "bidirectional"))
      (node (ref "S1") (pin "2") (pinfunction "S_2") (pintype "passive"))
    )
    (net (code "79") (name "VCC") (class "Default")
      (node (ref "C1") (pin "1") (pinfunction "1_1") (pintype "passive"))
      (node (ref "C2") (pin "1") (pinfunction "1_1") (pintype "passive"))
      (node (ref "C3") (pin "+") (pinfunction "+_+") (pintype "passive"))
      (node (ref "C5") (pin "1") (pinfunction "1_1") (pintype "passive"))
      (node (ref "C9") (pin "2") (pinfunction "2_2") (pintype "passive"))
      (node (ref "IC1") (pin "5") (pinfunction "VCC_5") (pintype "power_in"))
      (node (ref "IC2") (pin "10") (pinfunction "SCL_10") (pintype "input"))
      (node (ref "IC2") (pin "16") (pinfunction "VCC_16") (pintype "power_in"))
      (node (ref "IC4") (pin "9") (pinfunction "VCC_9") (pintype "power_in"))
      (node (ref "J1") (pin "1") (pinfunction "1_1") (pintype "passive"))
      (node (ref "L1") (pin "1") (pinfunction "1_1") (pintype "passive"))
      (node (ref "R39") (pin "2") (pinfunction "2_2") (pintype "passive"))
      (node (ref "R40") (pin "2") (pinfunction "2_2") (pintype "passive"))
      (node (ref "R41") (pin "2") (pinfunction "2_2") (pintype "passive"))
      (node (ref "SV1") (pin "VCC") (pinfunction "VCC_VCC") (pintype "power_in"))
      (node (ref "U1") (pin "8") (pinfunction "VCC_8") (pintype "bidirectional"))
    )
    (net (code "80") (name "unconnected-(IC2A-QH*-Pad9)") (class "Default")
      (node (ref "IC2") (pin "9") (pinfunction "QH*_9") (pintype "tri_state"))
    )
    (net (code "81") (name "unconnected-(IC4-OSCIN{slash}PA1-Pad5)") (class "Default")
      (node (ref "IC4") (pin "5") (pinfunction "OSCIN/PA1_5") (pintype "bidirectional"))
    )
    (net (code "82") (name "unconnected-(IC4-OSCOUT{slash}PA2-Pad6)") (class "Default")
      (node (ref "IC4") (pin "6") (pinfunction "OSCOUT/PA2_6") (pintype "bidirectional"))
    )
    (net (code "83") (name "unconnected-(J1-Pad2)") (class "Default")
      (node (ref "J1") (pin "2") (pinfunction "2_2") (pintype "passive"))
    )
    (net (code "84") (name "unconnected-(U1-SQW-Pad7)") (class "Default")
      (node (ref "U1") (pin "7") (pinfunction "SQW_7") (pintype "bidirectional"))
    )
  )
)
